# CM4_IO_Conn.net
KiCad netlist of a schematic drawn in Altium Designer
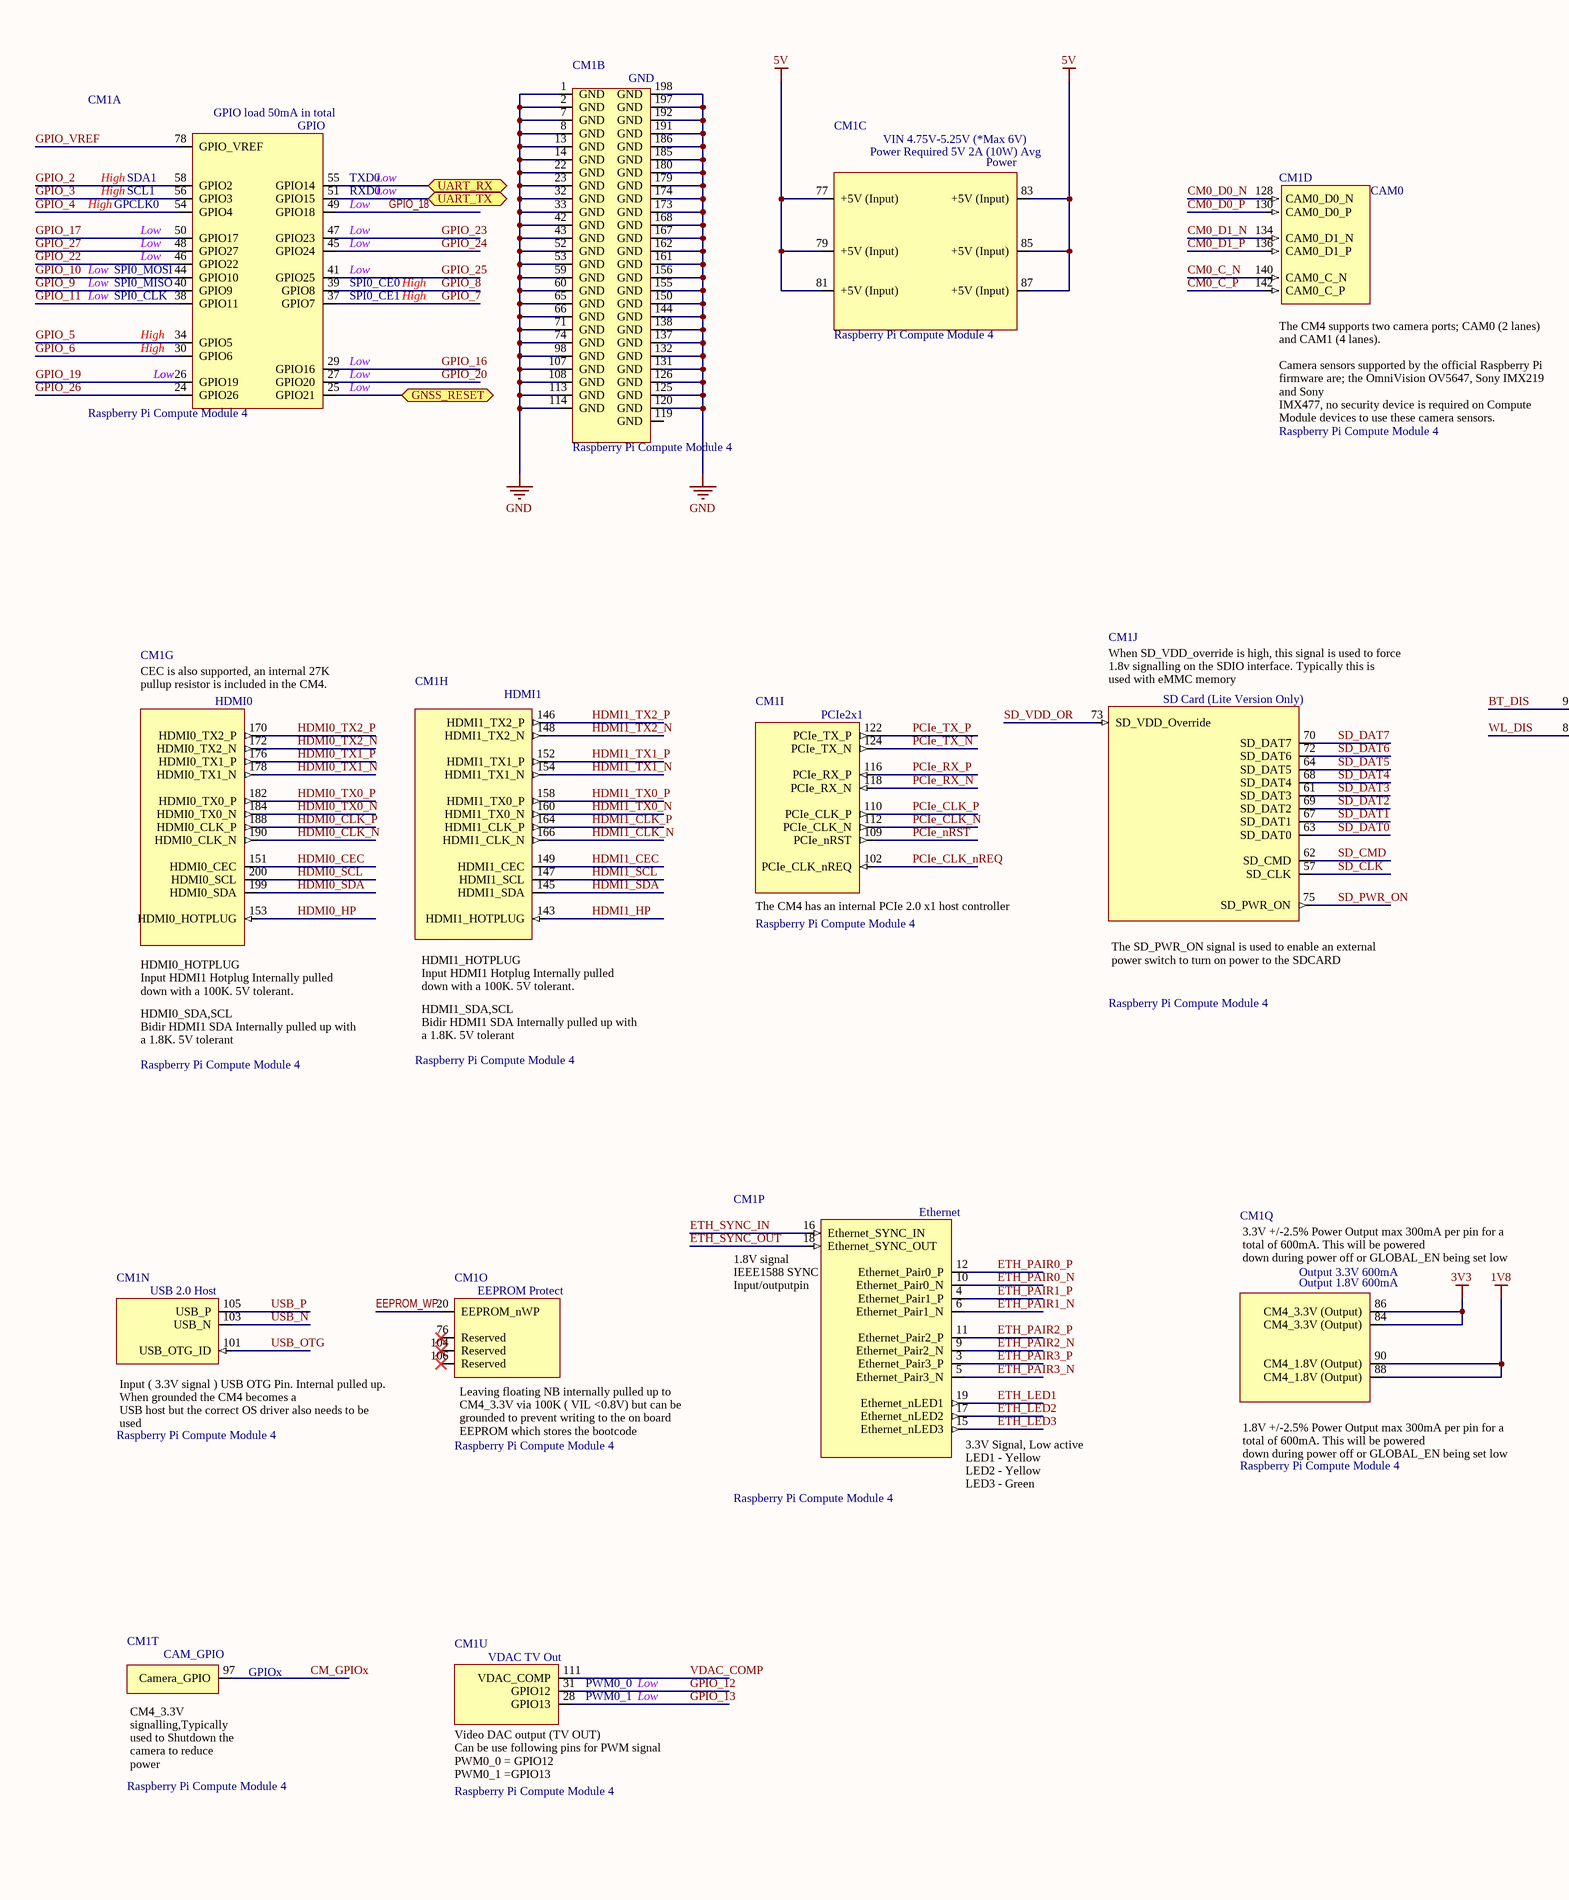
[diagram p0: CM4_IO_Conn.SchDoc, left]
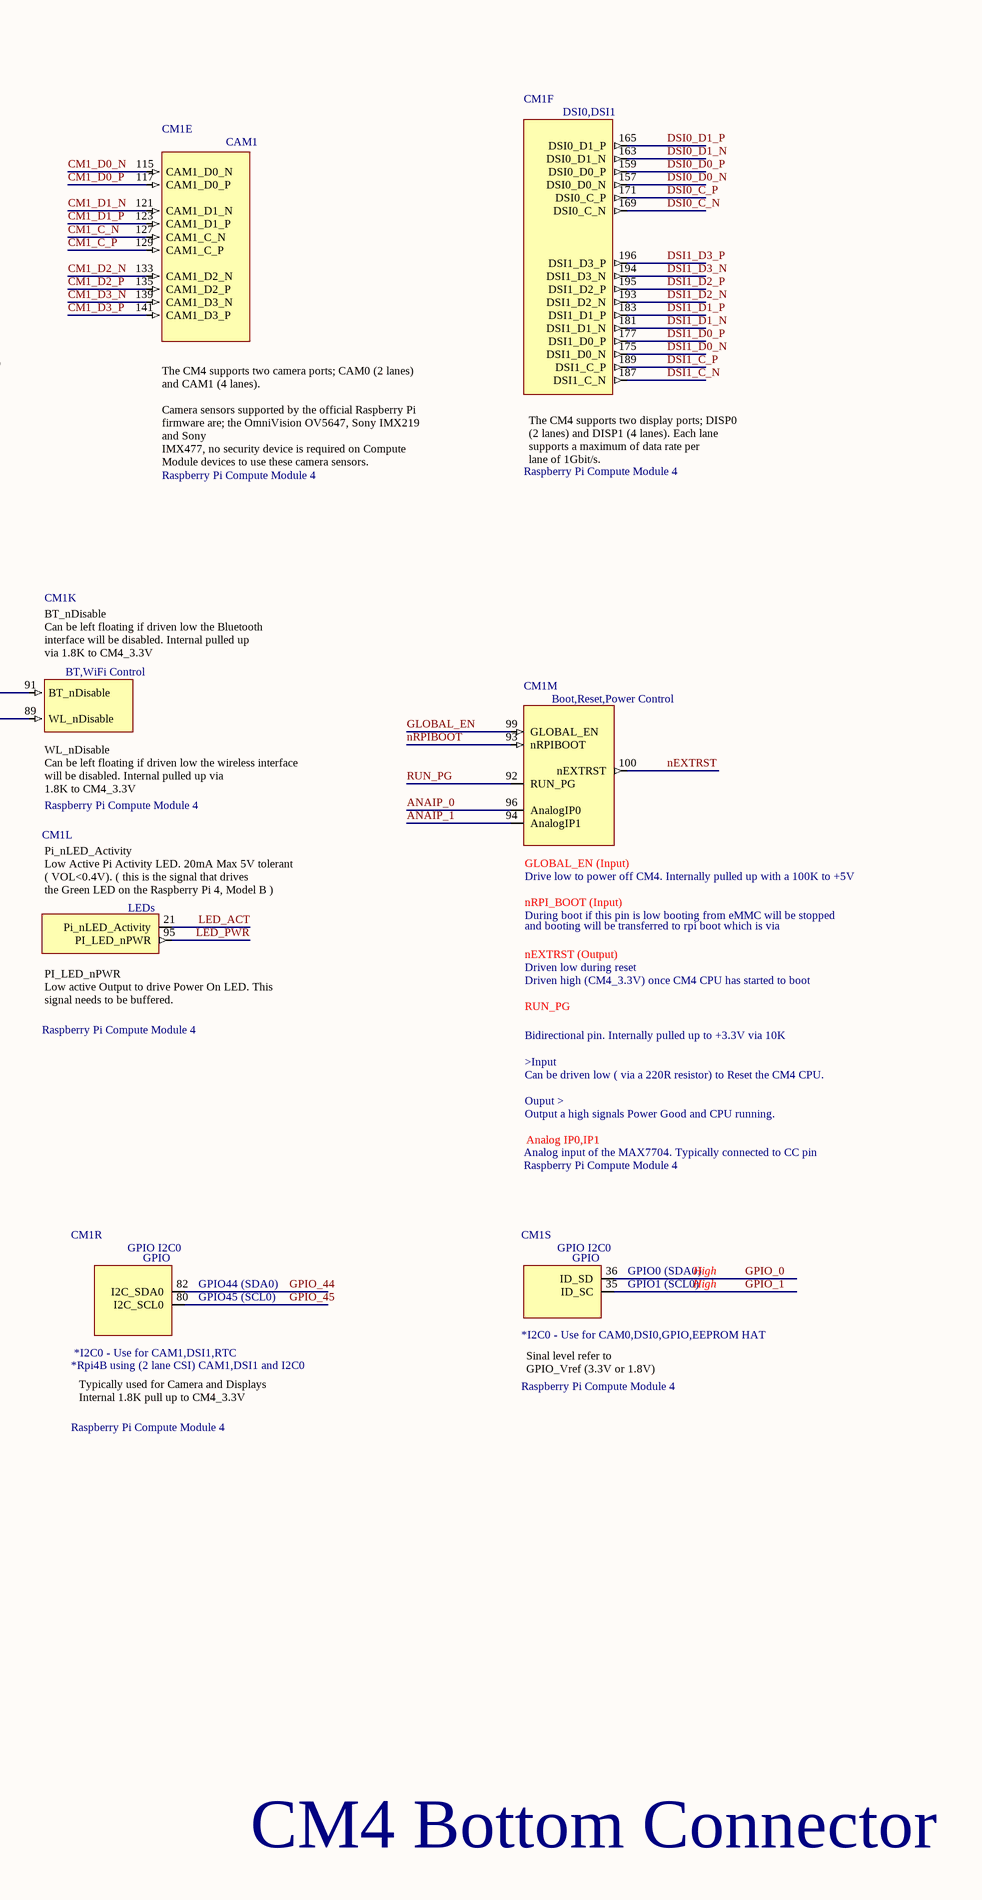
[diagram p1: CM4_IO_Conn.SchDoc, right]

(export (version "E")
  (design (tool "Eeschema 10.0.6"))
  (components
    (comp (ref "CM1")
      (value "Raspberry Pi Compute Module 4")
      (footprint "CM4-F40C-100DS-0.4v_1.5mm_0mm")
      (description "Raspberry Pi Compute Module 4 by Amornthep Phunsin")
      (libsource (lib "CM4") (part "CM4"))
    )
  )
  (nets
    (net (code "1") (name "/ANAIP_0") (class "Default")
      (node (ref "CM1") (pin "96") (pinfunction "AnalogIP0_96") (pintype "passive"))
    )
    (net (code "2") (name "/ANAIP_1") (class "Default")
      (node (ref "CM1") (pin "94") (pinfunction "AnalogIP1_94") (pintype "passive"))
    )
    (net (code "3") (name "/BT_DIS") (class "Default")
      (node (ref "CM1") (pin "91") (pinfunction "BT_nDisable_91") (pintype "input"))
    )
    (net (code "4") (name "/CM0_C_N") (class "Default")
      (node (ref "CM1") (pin "140") (pinfunction "CAM0_C_N_140") (pintype "input"))
    )
    (net (code "5") (name "/CM0_C_P") (class "Default")
      (node (ref "CM1") (pin "142") (pinfunction "CAM0_C_P_142") (pintype "input"))
    )
    (net (code "6") (name "/CM0_D0_N") (class "Default")
      (node (ref "CM1") (pin "128") (pinfunction "CAM0_D0_N_128") (pintype "input"))
    )
    (net (code "7") (name "/CM0_D0_P") (class "Default")
      (node (ref "CM1") (pin "130") (pinfunction "CAM0_D0_P_130") (pintype "input"))
    )
    (net (code "8") (name "/CM0_D1_N") (class "Default")
      (node (ref "CM1") (pin "134") (pinfunction "CAM0_D1_N_134") (pintype "input"))
    )
    (net (code "9") (name "/CM0_D1_P") (class "Default")
      (node (ref "CM1") (pin "136") (pinfunction "CAM0_D1_P_136") (pintype "input"))
    )
    (net (code "10") (name "/CM1_C_N") (class "Default")
      (node (ref "CM1") (pin "127") (pinfunction "CAM1_C_N_127") (pintype "input"))
    )
    (net (code "11") (name "/CM1_C_P") (class "Default")
      (node (ref "CM1") (pin "129") (pinfunction "CAM1_C_P_129") (pintype "input"))
    )
    (net (code "12") (name "/CM1_D0_N") (class "Default")
      (node (ref "CM1") (pin "115") (pinfunction "CAM1_D0_N_115") (pintype "input"))
    )
    (net (code "13") (name "/CM1_D0_P") (class "Default")
      (node (ref "CM1") (pin "117") (pinfunction "CAM1_D0_P_117") (pintype "input"))
    )
    (net (code "14") (name "/CM1_D1_N") (class "Default")
      (node (ref "CM1") (pin "121") (pinfunction "CAM1_D1_N_121") (pintype "input"))
    )
    (net (code "15") (name "/CM1_D1_P") (class "Default")
      (node (ref "CM1") (pin "123") (pinfunction "CAM1_D1_P_123") (pintype "input"))
    )
    (net (code "16") (name "/CM1_D2_N") (class "Default")
      (node (ref "CM1") (pin "133") (pinfunction "CAM1_D2_N_133") (pintype "input"))
    )
    (net (code "17") (name "/CM1_D2_P") (class "Default")
      (node (ref "CM1") (pin "135") (pinfunction "CAM1_D2_P_135") (pintype "input"))
    )
    (net (code "18") (name "/CM1_D3_N") (class "Default")
      (node (ref "CM1") (pin "139") (pinfunction "CAM1_D3_N_139") (pintype "input"))
    )
    (net (code "19") (name "/CM1_D3_P") (class "Default")
      (node (ref "CM1") (pin "141") (pinfunction "CAM1_D3_P_141") (pintype "input"))
    )
    (net (code "20") (name "/CM_GPIOx") (class "Default")
      (node (ref "CM1") (pin "97") (pinfunction "Camera_GPIO_97") (pintype "passive"))
    )
    (net (code "21") (name "/DSI0_C_N") (class "Default")
      (node (ref "CM1") (pin "169") (pinfunction "DSI0_C_N_169") (pintype "output"))
    )
    (net (code "22") (name "/DSI0_C_P") (class "Default")
      (node (ref "CM1") (pin "171") (pinfunction "DSI0_C_P_171") (pintype "output"))
    )
    (net (code "23") (name "/DSI0_D0_N") (class "Default")
      (node (ref "CM1") (pin "157") (pinfunction "DSI0_D0_N_157") (pintype "output"))
    )
    (net (code "24") (name "/DSI0_D0_P") (class "Default")
      (node (ref "CM1") (pin "159") (pinfunction "DSI0_D0_P_159") (pintype "output"))
    )
    (net (code "25") (name "/DSI0_D1_N") (class "Default")
      (node (ref "CM1") (pin "163") (pinfunction "DSI0_D1_N_163") (pintype "output"))
    )
    (net (code "26") (name "/DSI0_D1_P") (class "Default")
      (node (ref "CM1") (pin "165") (pinfunction "DSI0_D1_P_165") (pintype "output"))
    )
    (net (code "27") (name "/DSI1_C_N") (class "Default")
      (node (ref "CM1") (pin "187") (pinfunction "DSI1_C_N_187") (pintype "output"))
    )
    (net (code "28") (name "/DSI1_C_P") (class "Default")
      (node (ref "CM1") (pin "189") (pinfunction "DSI1_C_P_189") (pintype "output"))
    )
    (net (code "29") (name "/DSI1_D0_N") (class "Default")
      (node (ref "CM1") (pin "175") (pinfunction "DSI1_D0_N_175") (pintype "output"))
    )
    (net (code "30") (name "/DSI1_D0_P") (class "Default")
      (node (ref "CM1") (pin "177") (pinfunction "DSI1_D0_P_177") (pintype "output"))
    )
    (net (code "31") (name "/DSI1_D1_N") (class "Default")
      (node (ref "CM1") (pin "181") (pinfunction "DSI1_D1_N_181") (pintype "output"))
    )
    (net (code "32") (name "/DSI1_D1_P") (class "Default")
      (node (ref "CM1") (pin "183") (pinfunction "DSI1_D1_P_183") (pintype "output"))
    )
    (net (code "33") (name "/DSI1_D2_N") (class "Default")
      (node (ref "CM1") (pin "193") (pinfunction "DSI1_D2_N_193") (pintype "output"))
    )
    (net (code "34") (name "/DSI1_D2_P") (class "Default")
      (node (ref "CM1") (pin "195") (pinfunction "DSI1_D2_P_195") (pintype "output"))
    )
    (net (code "35") (name "/DSI1_D3_N") (class "Default")
      (node (ref "CM1") (pin "194") (pinfunction "DSI1_D3_N_194") (pintype "output"))
    )
    (net (code "36") (name "/DSI1_D3_P") (class "Default")
      (node (ref "CM1") (pin "196") (pinfunction "DSI1_D3_P_196") (pintype "output"))
    )
    (net (code "37") (name "/EEPROM_WP") (class "Default")
      (node (ref "CM1") (pin "20") (pinfunction "EEPROM_nWP_20") (pintype "passive"))
    )
    (net (code "38") (name "/ETH_LED1") (class "Default")
      (node (ref "CM1") (pin "19") (pinfunction "Ethernet_nLED1_19") (pintype "output"))
    )
    (net (code "39") (name "/ETH_LED2") (class "Default")
      (node (ref "CM1") (pin "17") (pinfunction "Ethernet_nLED2_17") (pintype "output"))
    )
    (net (code "40") (name "/ETH_LED3") (class "Default")
      (node (ref "CM1") (pin "15") (pinfunction "Ethernet_nLED3_15") (pintype "output"))
    )
    (net (code "41") (name "/ETH_PAIR0_N") (class "Default")
      (node (ref "CM1") (pin "10") (pinfunction "Ethernet_Pair0_N_10") (pintype "passive"))
    )
    (net (code "42") (name "/ETH_PAIR0_P") (class "Default")
      (node (ref "CM1") (pin "12") (pinfunction "Ethernet_Pair0_P_12") (pintype "passive"))
    )
    (net (code "43") (name "/ETH_PAIR1_N") (class "Default")
      (node (ref "CM1") (pin "6") (pinfunction "Ethernet_Pair1_N_6") (pintype "passive"))
    )
    (net (code "44") (name "/ETH_PAIR1_P") (class "Default")
      (node (ref "CM1") (pin "4") (pinfunction "Ethernet_Pair1_P_4") (pintype "passive"))
    )
    (net (code "45") (name "/ETH_PAIR2_N") (class "Default")
      (node (ref "CM1") (pin "9") (pinfunction "Ethernet_Pair2_N_9") (pintype "passive"))
    )
    (net (code "46") (name "/ETH_PAIR2_P") (class "Default")
      (node (ref "CM1") (pin "11") (pinfunction "Ethernet_Pair2_P_11") (pintype "passive"))
    )
    (net (code "47") (name "/ETH_PAIR3_N") (class "Default")
      (node (ref "CM1") (pin "5") (pinfunction "Ethernet_Pair3_N_5") (pintype "passive"))
    )
    (net (code "48") (name "/ETH_PAIR3_P") (class "Default")
      (node (ref "CM1") (pin "3") (pinfunction "Ethernet_Pair3_P_3") (pintype "passive"))
    )
    (net (code "49") (name "/ETH_SYNC_IN") (class "Default")
      (node (ref "CM1") (pin "16") (pinfunction "Ethernet_SYNC_IN_16") (pintype "input"))
    )
    (net (code "50") (name "/ETH_SYNC_OUT") (class "Default")
      (node (ref "CM1") (pin "18") (pinfunction "Ethernet_SYNC_OUT_18") (pintype "input"))
    )
    (net (code "51") (name "/GLOBAL_EN") (class "Default")
      (node (ref "CM1") (pin "99") (pinfunction "GLOBAL_EN_99") (pintype "input"))
    )
    (net (code "52") (name "/GNSS_RESET") (class "Default")
      (node (ref "CM1") (pin "25") (pinfunction "GPIO21_25") (pintype "passive"))
    )
    (net (code "53") (name "/GPIO_0") (class "Default")
      (node (ref "CM1") (pin "36") (pinfunction "ID_SD_36") (pintype "passive"))
    )
    (net (code "54") (name "/GPIO_1") (class "Default")
      (node (ref "CM1") (pin "35") (pinfunction "ID_SC_35") (pintype "passive"))
    )
    (net (code "55") (name "/GPIO_2") (class "Default")
      (node (ref "CM1") (pin "58") (pinfunction "GPIO2_58") (pintype "passive"))
    )
    (net (code "56") (name "/GPIO_3") (class "Default")
      (node (ref "CM1") (pin "56") (pinfunction "GPIO3_56") (pintype "passive"))
    )
    (net (code "57") (name "/GPIO_4") (class "Default")
      (node (ref "CM1") (pin "54") (pinfunction "GPIO4_54") (pintype "passive"))
    )
    (net (code "58") (name "/GPIO_5") (class "Default")
      (node (ref "CM1") (pin "34") (pinfunction "GPIO5_34") (pintype "passive"))
    )
    (net (code "59") (name "/GPIO_6") (class "Default")
      (node (ref "CM1") (pin "30") (pinfunction "GPIO6_30") (pintype "passive"))
    )
    (net (code "60") (name "/GPIO_7") (class "Default")
      (node (ref "CM1") (pin "37") (pinfunction "GPIO7_37") (pintype "passive"))
    )
    (net (code "61") (name "/GPIO_8") (class "Default")
      (node (ref "CM1") (pin "39") (pinfunction "GPIO8_39") (pintype "passive"))
    )
    (net (code "62") (name "/GPIO_9") (class "Default")
      (node (ref "CM1") (pin "40") (pinfunction "GPIO9_40") (pintype "passive"))
    )
    (net (code "63") (name "/GPIO_10") (class "Default")
      (node (ref "CM1") (pin "44") (pinfunction "GPIO10_44") (pintype "passive"))
    )
    (net (code "64") (name "/GPIO_11") (class "Default")
      (node (ref "CM1") (pin "38") (pinfunction "GPIO11_38") (pintype "passive"))
    )
    (net (code "65") (name "/GPIO_12") (class "Default")
      (node (ref "CM1") (pin "31") (pinfunction "GPIO12_31") (pintype "passive"))
    )
    (net (code "66") (name "/GPIO_13") (class "Default")
      (node (ref "CM1") (pin "28") (pinfunction "GPIO13_28") (pintype "passive"))
    )
    (net (code "67") (name "/GPIO_16") (class "Default")
      (node (ref "CM1") (pin "29") (pinfunction "GPIO16_29") (pintype "passive"))
    )
    (net (code "68") (name "/GPIO_17") (class "Default")
      (node (ref "CM1") (pin "50") (pinfunction "GPIO17_50") (pintype "passive"))
    )
    (net (code "69") (name "/GPIO_18") (class "Default")
      (node (ref "CM1") (pin "49") (pinfunction "GPIO18_49") (pintype "passive"))
    )
    (net (code "70") (name "/GPIO_19") (class "Default")
      (node (ref "CM1") (pin "26") (pinfunction "GPIO19_26") (pintype "passive"))
    )
    (net (code "71") (name "/GPIO_20") (class "Default")
      (node (ref "CM1") (pin "27") (pinfunction "GPIO20_27") (pintype "passive"))
    )
    (net (code "72") (name "/GPIO_22") (class "Default")
      (node (ref "CM1") (pin "46") (pinfunction "GPIO22_46") (pintype "passive"))
    )
    (net (code "73") (name "/GPIO_23") (class "Default")
      (node (ref "CM1") (pin "47") (pinfunction "GPIO23_47") (pintype "passive"))
    )
    (net (code "74") (name "/GPIO_24") (class "Default")
      (node (ref "CM1") (pin "45") (pinfunction "GPIO24_45") (pintype "passive"))
    )
    (net (code "75") (name "/GPIO_25") (class "Default")
      (node (ref "CM1") (pin "41") (pinfunction "GPIO25_41") (pintype "passive"))
    )
    (net (code "76") (name "/GPIO_26") (class "Default")
      (node (ref "CM1") (pin "24") (pinfunction "GPIO26_24") (pintype "passive"))
    )
    (net (code "77") (name "/GPIO_27") (class "Default")
      (node (ref "CM1") (pin "48") (pinfunction "GPIO27_48") (pintype "passive"))
    )
    (net (code "78") (name "/GPIO_44") (class "Default")
      (node (ref "CM1") (pin "82") (pinfunction "I2C_SDA0_82") (pintype "passive"))
    )
    (net (code "79") (name "/GPIO_45") (class "Default")
      (node (ref "CM1") (pin "80") (pinfunction "I2C_SCL0_80") (pintype "passive"))
    )
    (net (code "80") (name "/GPIO_VREF") (class "Default")
      (node (ref "CM1") (pin "78") (pinfunction "GPIO_VREF_78") (pintype "power_in"))
    )
    (net (code "81") (name "/HDMI0_CEC") (class "Default")
      (node (ref "CM1") (pin "151") (pinfunction "HDMI0_CEC_151") (pintype "open_collector"))
    )
    (net (code "82") (name "/HDMI0_CLK_N") (class "Default")
      (node (ref "CM1") (pin "190") (pinfunction "HDMI0_CLK_N_190") (pintype "output"))
    )
    (net (code "83") (name "/HDMI0_CLK_P") (class "Default")
      (node (ref "CM1") (pin "188") (pinfunction "HDMI0_CLK_P_188") (pintype "output"))
    )
    (net (code "84") (name "/HDMI0_HP") (class "Default")
      (node (ref "CM1") (pin "153") (pinfunction "HDMI0_HOTPLUG_153") (pintype "input"))
    )
    (net (code "85") (name "/HDMI0_SCL") (class "Default")
      (node (ref "CM1") (pin "200") (pinfunction "HDMI0_SCL_200") (pintype "open_collector"))
    )
    (net (code "86") (name "/HDMI0_SDA") (class "Default")
      (node (ref "CM1") (pin "199") (pinfunction "HDMI0_SDA_199") (pintype "bidirectional"))
    )
    (net (code "87") (name "/HDMI0_TX0_N") (class "Default")
      (node (ref "CM1") (pin "184") (pinfunction "HDMI0_TX0_N_184") (pintype "output"))
    )
    (net (code "88") (name "/HDMI0_TX0_P") (class "Default")
      (node (ref "CM1") (pin "182") (pinfunction "HDMI0_TX0_P_182") (pintype "output"))
    )
    (net (code "89") (name "/HDMI0_TX1_N") (class "Default")
      (node (ref "CM1") (pin "178") (pinfunction "HDMI0_TX1_N_178") (pintype "output"))
    )
    (net (code "90") (name "/HDMI0_TX1_P") (class "Default")
      (node (ref "CM1") (pin "176") (pinfunction "HDMI0_TX1_P_176") (pintype "output"))
    )
    (net (code "91") (name "/HDMI0_TX2_N") (class "Default")
      (node (ref "CM1") (pin "172") (pinfunction "HDMI0_TX2_N_172") (pintype "output"))
    )
    (net (code "92") (name "/HDMI0_TX2_P") (class "Default")
      (node (ref "CM1") (pin "170") (pinfunction "HDMI0_TX2_P_170") (pintype "output"))
    )
    (net (code "93") (name "/HDMI1_CEC") (class "Default")
      (node (ref "CM1") (pin "149") (pinfunction "HDMI1_CEC_149") (pintype "open_collector"))
    )
    (net (code "94") (name "/HDMI1_CLK_N") (class "Default")
      (node (ref "CM1") (pin "166") (pinfunction "HDMI1_CLK_N_166") (pintype "output"))
    )
    (net (code "95") (name "/HDMI1_CLK_P") (class "Default")
      (node (ref "CM1") (pin "164") (pinfunction "HDMI1_CLK_P_164") (pintype "output"))
    )
    (net (code "96") (name "/HDMI1_HP") (class "Default")
      (node (ref "CM1") (pin "143") (pinfunction "HDMI1_HOTPLUG_143") (pintype "input"))
    )
    (net (code "97") (name "/HDMI1_SCL") (class "Default")
      (node (ref "CM1") (pin "147") (pinfunction "HDMI1_SCL_147") (pintype "open_collector"))
    )
    (net (code "98") (name "/HDMI1_SDA") (class "Default")
      (node (ref "CM1") (pin "145") (pinfunction "HDMI1_SDA_145") (pintype "bidirectional"))
    )
    (net (code "99") (name "/HDMI1_TX0_N") (class "Default")
      (node (ref "CM1") (pin "160") (pinfunction "HDMI1_TX0_N_160") (pintype "output"))
    )
    (net (code "100") (name "/HDMI1_TX0_P") (class "Default")
      (node (ref "CM1") (pin "158") (pinfunction "HDMI1_TX0_P_158") (pintype "output"))
    )
    (net (code "101") (name "/HDMI1_TX1_N") (class "Default")
      (node (ref "CM1") (pin "154") (pinfunction "HDMI1_TX1_N_154") (pintype "output"))
    )
    (net (code "102") (name "/HDMI1_TX1_P") (class "Default")
      (node (ref "CM1") (pin "152") (pinfunction "HDMI1_TX1_P_152") (pintype "output"))
    )
    (net (code "103") (name "/HDMI1_TX2_N") (class "Default")
      (node (ref "CM1") (pin "148") (pinfunction "HDMI1_TX2_N_148") (pintype "output"))
    )
    (net (code "104") (name "/HDMI1_TX2_P") (class "Default")
      (node (ref "CM1") (pin "146") (pinfunction "HDMI1_TX2_P_146") (pintype "output"))
    )
    (net (code "105") (name "/LED_ACT") (class "Default")
      (node (ref "CM1") (pin "21") (pinfunction "Pi_nLED_Activity_21") (pintype "open_collector"))
    )
    (net (code "106") (name "/LED_PWR") (class "Default")
      (node (ref "CM1") (pin "95") (pinfunction "PI_LED_nPWR_95") (pintype "output"))
    )
    (net (code "107") (name "/PCIe_CLK_N") (class "Default")
      (node (ref "CM1") (pin "112") (pinfunction "PCIe_CLK_N_112") (pintype "output"))
    )
    (net (code "108") (name "/PCIe_CLK_P") (class "Default")
      (node (ref "CM1") (pin "110") (pinfunction "PCIe_CLK_P_110") (pintype "output"))
    )
    (net (code "109") (name "/PCIe_CLK_nREQ") (class "Default")
      (node (ref "CM1") (pin "102") (pinfunction "PCIe_CLK_nREQ_102") (pintype "input"))
    )
    (net (code "110") (name "/PCIe_RX_N") (class "Default")
      (node (ref "CM1") (pin "118") (pinfunction "PCIe_RX_N_118") (pintype "input"))
    )
    (net (code "111") (name "/PCIe_RX_P") (class "Default")
      (node (ref "CM1") (pin "116") (pinfunction "PCIe_RX_P_116") (pintype "input"))
    )
    (net (code "112") (name "/PCIe_TX_N") (class "Default")
      (node (ref "CM1") (pin "124") (pinfunction "PCIe_TX_N_124") (pintype "output"))
    )
    (net (code "113") (name "/PCIe_TX_P") (class "Default")
      (node (ref "CM1") (pin "122") (pinfunction "PCIe_TX_P_122") (pintype "output"))
    )
    (net (code "114") (name "/PCIe_nRST") (class "Default")
      (node (ref "CM1") (pin "109") (pinfunction "PCIe_nRST_109") (pintype "output"))
    )
    (net (code "115") (name "/RUN_PG") (class "Default")
      (node (ref "CM1") (pin "92") (pinfunction "RUN_PG_92") (pintype "passive"))
    )
    (net (code "116") (name "/SD_CLK") (class "Default")
      (node (ref "CM1") (pin "57") (pinfunction "SD_CLK_57") (pintype "passive"))
    )
    (net (code "117") (name "/SD_CMD") (class "Default")
      (node (ref "CM1") (pin "62") (pinfunction "SD_CMD_62") (pintype "passive"))
    )
    (net (code "118") (name "/SD_DAT0") (class "Default")
      (node (ref "CM1") (pin "63") (pinfunction "SD_DAT0_63") (pintype "passive"))
    )
    (net (code "119") (name "/SD_DAT1") (class "Default")
      (node (ref "CM1") (pin "67") (pinfunction "SD_DAT1_67") (pintype "passive"))
    )
    (net (code "120") (name "/SD_DAT2") (class "Default")
      (node (ref "CM1") (pin "69") (pinfunction "SD_DAT2_69") (pintype "passive"))
    )
    (net (code "121") (name "/SD_DAT3") (class "Default")
      (node (ref "CM1") (pin "61") (pinfunction "SD_DAT3_61") (pintype "passive"))
    )
    (net (code "122") (name "/SD_DAT4") (class "Default")
      (node (ref "CM1") (pin "68") (pinfunction "SD_DAT4_68") (pintype "passive"))
    )
    (net (code "123") (name "/SD_DAT5") (class "Default")
      (node (ref "CM1") (pin "64") (pinfunction "SD_DAT5_64") (pintype "passive"))
    )
    (net (code "124") (name "/SD_DAT6") (class "Default")
      (node (ref "CM1") (pin "72") (pinfunction "SD_DAT6_72") (pintype "passive"))
    )
    (net (code "125") (name "/SD_DAT7") (class "Default")
      (node (ref "CM1") (pin "70") (pinfunction "SD_DAT7_70") (pintype "passive"))
    )
    (net (code "126") (name "/SD_PWR_ON") (class "Default")
      (node (ref "CM1") (pin "75") (pinfunction "SD_PWR_ON_75") (pintype "output"))
    )
    (net (code "127") (name "/SD_VDD_OR") (class "Default")
      (node (ref "CM1") (pin "73") (pinfunction "SD_VDD_Override_73") (pintype "input"))
    )
    (net (code "128") (name "/UART_RX") (class "Default")
      (node (ref "CM1") (pin "55") (pinfunction "GPIO14_55") (pintype "passive"))
    )
    (net (code "129") (name "/UART_TX") (class "Default")
      (node (ref "CM1") (pin "51") (pinfunction "GPIO15_51") (pintype "passive"))
    )
    (net (code "130") (name "/USB_N") (class "Default")
      (node (ref "CM1") (pin "103") (pinfunction "USB_N_103") (pintype "passive"))
    )
    (net (code "131") (name "/USB_OTG") (class "Default")
      (node (ref "CM1") (pin "101") (pinfunction "USB_OTG_ID_101") (pintype "input"))
    )
    (net (code "132") (name "/USB_P") (class "Default")
      (node (ref "CM1") (pin "105") (pinfunction "USB_P_105") (pintype "passive"))
    )
    (net (code "133") (name "/VDAC_COMP") (class "Default")
      (node (ref "CM1") (pin "111") (pinfunction "VDAC_COMP_111") (pintype "passive"))
    )
    (net (code "134") (name "/WL_DIS") (class "Default")
      (node (ref "CM1") (pin "89") (pinfunction "WL_nDisable_89") (pintype "input"))
    )
    (net (code "135") (name "/nEXTRST") (class "Default")
      (node (ref "CM1") (pin "100") (pinfunction "nEXTRST_100") (pintype "output"))
    )
    (net (code "136") (name "/nRPIBOOT") (class "Default")
      (node (ref "CM1") (pin "93") (pinfunction "nRPIBOOT_93") (pintype "input"))
    )
    (net (code "137") (name "1V8") (class "Default")
      (node (ref "CM1") (pin "88") (pinfunction "CM4_1.8V_(Output)_88") (pintype "power_in"))
      (node (ref "CM1") (pin "90") (pinfunction "CM4_1.8V_(Output)_90") (pintype "power_in"))
    )
    (net (code "138") (name "3V3") (class "Default")
      (node (ref "CM1") (pin "84") (pinfunction "CM4_3.3V_(Output)_84") (pintype "power_in"))
      (node (ref "CM1") (pin "86") (pinfunction "CM4_3.3V_(Output)_86") (pintype "power_in"))
    )
    (net (code "139") (name "5V") (class "Default")
      (node (ref "CM1") (pin "77") (pinfunction "+5V_(Input)_77") (pintype "power_in"))
      (node (ref "CM1") (pin "79") (pinfunction "+5V_(Input)_79") (pintype "power_in"))
      (node (ref "CM1") (pin "81") (pinfunction "+5V_(Input)_81") (pintype "power_in"))
      (node (ref "CM1") (pin "83") (pinfunction "+5V_(Input)_83") (pintype "power_in"))
      (node (ref "CM1") (pin "85") (pinfunction "+5V_(Input)_85") (pintype "power_in"))
      (node (ref "CM1") (pin "87") (pinfunction "+5V_(Input)_87") (pintype "power_in"))
    )
    (net (code "140") (name "GND") (class "Default")
      (node (ref "CM1") (pin "1") (pinfunction "GND_1") (pintype "power_in"))
      (node (ref "CM1") (pin "107") (pinfunction "GND_107") (pintype "power_in"))
      (node (ref "CM1") (pin "108") (pinfunction "GND_108") (pintype "power_in"))
      (node (ref "CM1") (pin "113") (pinfunction "GND_113") (pintype "power_in"))
      (node (ref "CM1") (pin "114") (pinfunction "GND_114") (pintype "power_in"))
      (node (ref "CM1") (pin "120") (pinfunction "GND_120") (pintype "power_in"))
      (node (ref "CM1") (pin "125") (pinfunction "GND_125") (pintype "power_in"))
      (node (ref "CM1") (pin "126") (pinfunction "GND_126") (pintype "power_in"))
      (node (ref "CM1") (pin "13") (pinfunction "GND_13") (pintype "power_in"))
      (node (ref "CM1") (pin "131") (pinfunction "GND_131") (pintype "power_in"))
      (node (ref "CM1") (pin "132") (pinfunction "GND_132") (pintype "power_in"))
      (node (ref "CM1") (pin "137") (pinfunction "GND_137") (pintype "power_in"))
      (node (ref "CM1") (pin "138") (pinfunction "GND_138") (pintype "power_in"))
      (node (ref "CM1") (pin "14") (pinfunction "GND_14") (pintype "power_in"))
      (node (ref "CM1") (pin "144") (pinfunction "GND_144") (pintype "power_in"))
      (node (ref "CM1") (pin "150") (pinfunction "GND_150") (pintype "power_in"))
      (node (ref "CM1") (pin "155") (pinfunction "GND_155") (pintype "power_in"))
      (node (ref "CM1") (pin "156") (pinfunction "GND_156") (pintype "power_in"))
      (node (ref "CM1") (pin "161") (pinfunction "GND_161") (pintype "power_in"))
      (node (ref "CM1") (pin "162") (pinfunction "GND_162") (pintype "power_in"))
      (node (ref "CM1") (pin "167") (pinfunction "GND_167") (pintype "power_in"))
      (node (ref "CM1") (pin "168") (pinfunction "GND_168") (pintype "power_in"))
      (node (ref "CM1") (pin "173") (pinfunction "GND_173") (pintype "power_in"))
      (node (ref "CM1") (pin "174") (pinfunction "GND_174") (pintype "power_in"))
      (node (ref "CM1") (pin "179") (pinfunction "GND_179") (pintype "power_in"))
      (node (ref "CM1") (pin "180") (pinfunction "GND_180") (pintype "power_in"))
      (node (ref "CM1") (pin "185") (pinfunction "GND_185") (pintype "power_in"))
      (node (ref "CM1") (pin "186") (pinfunction "GND_186") (pintype "power_in"))
      (node (ref "CM1") (pin "191") (pinfunction "GND_191") (pintype "power_in"))
      (node (ref "CM1") (pin "192") (pinfunction "GND_192") (pintype "power_in"))
      (node (ref "CM1") (pin "197") (pinfunction "GND_197") (pintype "power_in"))
      (node (ref "CM1") (pin "198") (pinfunction "GND_198") (pintype "power_in"))
      (node (ref "CM1") (pin "2") (pinfunction "GND_2") (pintype "power_in"))
      (node (ref "CM1") (pin "22") (pinfunction "GND_22") (pintype "power_in"))
      (node (ref "CM1") (pin "23") (pinfunction "GND_23") (pintype "power_in"))
      (node (ref "CM1") (pin "32") (pinfunction "GND_32") (pintype "power_in"))
      (node (ref "CM1") (pin "33") (pinfunction "GND_33") (pintype "power_in"))
      (node (ref "CM1") (pin "42") (pinfunction "GND_42") (pintype "power_in"))
      (node (ref "CM1") (pin "43") (pinfunction "GND_43") (pintype "power_in"))
      (node (ref "CM1") (pin "52") (pinfunction "GND_52") (pintype "power_in"))
      (node (ref "CM1") (pin "53") (pinfunction "GND_53") (pintype "power_in"))
      (node (ref "CM1") (pin "59") (pinfunction "GND_59") (pintype "power_in"))
      (node (ref "CM1") (pin "60") (pinfunction "GND_60") (pintype "power_in"))
      (node (ref "CM1") (pin "65") (pinfunction "GND_65") (pintype "power_in"))
      (node (ref "CM1") (pin "66") (pinfunction "GND_66") (pintype "power_in"))
      (node (ref "CM1") (pin "7") (pinfunction "GND_7") (pintype "power_in"))
      (node (ref "CM1") (pin "71") (pinfunction "GND_71") (pintype "power_in"))
      (node (ref "CM1") (pin "74") (pinfunction "GND_74") (pintype "power_in"))
      (node (ref "CM1") (pin "8") (pinfunction "GND_8") (pintype "power_in"))
      (node (ref "CM1") (pin "98") (pinfunction "GND_98") (pintype "power_in"))
    )
    (net (code "141") (name "unconnected-(CM1B-GND-Pad119)") (class "Default")
      (node (ref "CM1") (pin "119") (pinfunction "GND_119") (pintype "power_in"))
    )
    (net (code "142") (name "unconnected-(CM1O-Reserved-Pad76)") (class "Default")
      (node (ref "CM1") (pin "76") (pinfunction "Reserved_76") (pintype "passive+no_connect"))
    )
    (net (code "143") (name "unconnected-(CM1O-Reserved-Pad104)") (class "Default")
      (node (ref "CM1") (pin "104") (pinfunction "Reserved_104") (pintype "passive+no_connect"))
    )
    (net (code "144") (name "unconnected-(CM1O-Reserved-Pad106)") (class "Default")
      (node (ref "CM1") (pin "106") (pinfunction "Reserved_106") (pintype "passive+no_connect"))
    )
  )
)
